# 5.net
KiCad netlist of a schematic drawn in Altium Designer
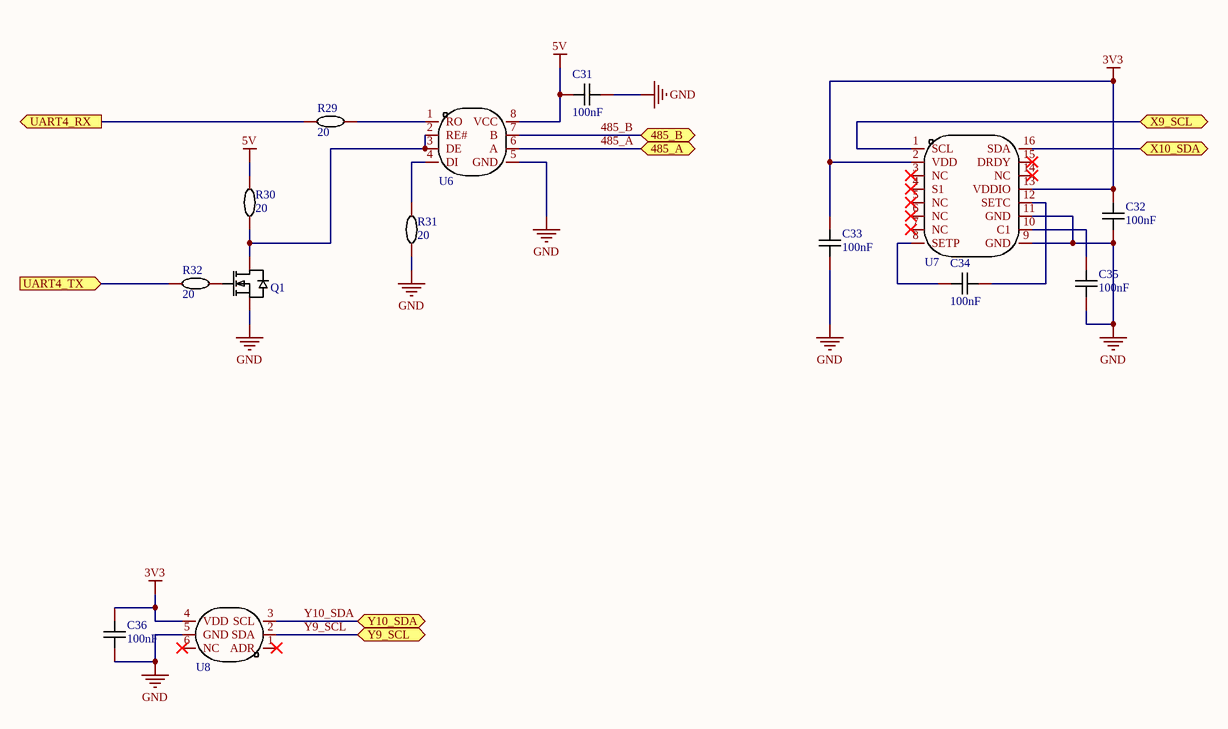
[diagram p0: 5_传感器.SchDoc]

(export (version "E")
  (design (tool "Eeschema 10.0.6"))
  (components
    (comp (ref "C31")
      (value "100nF")
      (footprint "0402C")
      (fields (field (name "NAME") "100nF"))
      (libsource (lib "2_传感器.schdoc") (part "CAP_0402"))
    )
    (comp (ref "C32")
      (value "100nF")
      (footprint "0402C")
      (fields (field (name "NAME") "100nF"))
      (libsource (lib "2_传感器.schdoc") (part "CAP_0402"))
    )
    (comp (ref "C33")
      (value "100nF")
      (footprint "0402C")
      (fields (field (name "NAME") "100nF"))
      (libsource (lib "2_传感器.schdoc") (part "CAP_0402"))
    )
    (comp (ref "C34")
      (value "100nF")
      (footprint "0402C")
      (fields (field (name "NAME") "100nF"))
      (libsource (lib "2_传感器.schdoc") (part "CAP_0402"))
    )
    (comp (ref "C35")
      (value "100nF")
      (footprint "0402C")
      (fields (field (name "NAME") "100nF"))
      (libsource (lib "2_传感器.schdoc") (part "CAP_0402"))
    )
    (comp (ref "C36")
      (value "100nF")
      (footprint "0402C")
      (fields (field (name "NAME") "100nF"))
      (libsource (lib "2_传感器.schdoc") (part "CAP_0402"))
    )
    (comp (ref "Q1")
      (value "2N7002")
      (footprint "SOT-23-3_L2.9-W1.3-P1.90-LS2.4-BR")
      (libsource (lib "2_传感器.schdoc") (part "2N7002_C8545"))
    )
    (comp (ref "R29")
      (value "20")
      (footprint "0402R")
      (fields (field (name "NAME") "20"))
      (libsource (lib "2_传感器.schdoc") (part "Res_0402"))
    )
    (comp (ref "R30")
      (value "20")
      (footprint "0402R")
      (fields (field (name "NAME") "20"))
      (libsource (lib "2_传感器.schdoc") (part "Res_0402"))
    )
    (comp (ref "R31")
      (value "20")
      (footprint "0402R")
      (fields (field (name "NAME") "20"))
      (libsource (lib "2_传感器.schdoc") (part "Res_0402"))
    )
    (comp (ref "R32")
      (value "20")
      (footprint "0402R")
      (fields (field (name "NAME") "20"))
      (libsource (lib "2_传感器.schdoc") (part "Res_0402"))
    )
    (comp (ref "U6")
      (value "MAX3485ECSA+")
      (footprint "SOIC-8_L4.9-W3.9-P1.27-LS6.0-BL")
      (libsource (lib "2_传感器.schdoc") (part "MAX3485ECSA+"))
    )
    (comp (ref "U7")
      (value "QMC5883L")
      (footprint "LGA-16_L3.0-W3.0-P0.50-BL_SQ")
      (libsource (lib "2_传感器.schdoc") (part "QMC5883L"))
    )
    (comp (ref "U8")
      (value "AHT10")
      (footprint "SENSOR-SMD_AHT10")
      (libsource (lib "2_传感器.schdoc") (part "AHT10"))
    )
  )
  (nets
    (net (code "1") (name "/485_A") (class "Default")
      (node (ref "U6") (pin "6") (pinfunction "A_6") (pintype "passive"))
    )
    (net (code "2") (name "/485_B") (class "Default")
      (node (ref "U6") (pin "7") (pinfunction "B_7") (pintype "passive"))
    )
    (net (code "3") (name "/UART4_RX") (class "Default")
      (node (ref "R29") (pin "1") (pinfunction "1_1") (pintype "passive"))
    )
    (net (code "4") (name "/UART4_TX") (class "Default")
      (node (ref "R32") (pin "1") (pinfunction "1_1") (pintype "passive"))
    )
    (net (code "5") (name "/X9_SCL") (class "Default")
      (node (ref "U7") (pin "1") (pinfunction "SCL_1") (pintype "passive"))
    )
    (net (code "6") (name "/X10_SDA") (class "Default")
      (node (ref "U7") (pin "16") (pinfunction "SDA_16") (pintype "passive"))
    )
    (net (code "7") (name "/Y9_SCL") (class "Default")
      (node (ref "U8") (pin "2") (pinfunction "SDA_2") (pintype "passive"))
    )
    (net (code "8") (name "/Y10_SDA") (class "Default")
      (node (ref "U8") (pin "3") (pinfunction "SCL_3") (pintype "passive"))
    )
    (net (code "9") (name "3V3") (class "Default")
      (node (ref "C32") (pin "1") (pinfunction "1_1") (pintype "passive"))
      (node (ref "C33") (pin "2") (pinfunction "2_2") (pintype "passive"))
      (node (ref "C36") (pin "1") (pinfunction "1_1") (pintype "passive"))
      (node (ref "U7") (pin "13") (pinfunction "VDDIO_13") (pintype "passive"))
      (node (ref "U7") (pin "2") (pinfunction "VDD_2") (pintype "passive"))
      (node (ref "U8") (pin "4") (pinfunction "VDD_4") (pintype "passive"))
    )
    (net (code "10") (name "5V") (class "Default")
      (node (ref "C31") (pin "2") (pinfunction "2_2") (pintype "passive"))
      (node (ref "R30") (pin "2") (pinfunction "2_2") (pintype "passive"))
      (node (ref "U6") (pin "8") (pinfunction "VCC_8") (pintype "passive"))
    )
    (net (code "11") (name "GND") (class "Default")
      (node (ref "C31") (pin "1") (pinfunction "1_1") (pintype "passive"))
      (node (ref "C32") (pin "2") (pinfunction "2_2") (pintype "passive"))
      (node (ref "C33") (pin "1") (pinfunction "1_1") (pintype "passive"))
      (node (ref "C35") (pin "2") (pinfunction "2_2") (pintype "passive"))
      (node (ref "C36") (pin "2") (pinfunction "2_2") (pintype "passive"))
      (node (ref "Q1") (pin "2") (pinfunction "S_2") (pintype "passive"))
      (node (ref "R31") (pin "1") (pinfunction "1_1") (pintype "passive"))
      (node (ref "U6") (pin "5") (pinfunction "GND_5") (pintype "passive"))
      (node (ref "U7") (pin "11") (pinfunction "GND_11") (pintype "passive"))
      (node (ref "U7") (pin "9") (pinfunction "GND_9") (pintype "passive"))
      (node (ref "U8") (pin "5") (pinfunction "GND_5") (pintype "passive"))
    )
    (net (code "12") (name "Net-(Q1-D)") (class "Default")
      (node (ref "Q1") (pin "3") (pinfunction "D_3") (pintype "passive"))
      (node (ref "R30") (pin "1") (pinfunction "1_1") (pintype "passive"))
      (node (ref "U6") (pin "2") (pinfunction "RE#_2") (pintype "passive"))
      (node (ref "U6") (pin "3") (pinfunction "DE_3") (pintype "passive"))
    )
    (net (code "13") (name "Net-(U6-DI)") (class "Default")
      (node (ref "R31") (pin "2") (pinfunction "2_2") (pintype "passive"))
      (node (ref "U6") (pin "4") (pinfunction "DI_4") (pintype "passive"))
    )
    (net (code "14") (name "Net-(U6-RO)") (class "Default")
      (node (ref "R29") (pin "2") (pinfunction "2_2") (pintype "passive"))
      (node (ref "U6") (pin "1") (pinfunction "RO_1") (pintype "passive"))
    )
    (net (code "15") (name "Net-(U7-C1)") (class "Default")
      (node (ref "C35") (pin "1") (pinfunction "1_1") (pintype "passive"))
      (node (ref "U7") (pin "10") (pinfunction "C1_10") (pintype "passive"))
    )
    (net (code "16") (name "Net-(U7-SETC)") (class "Default")
      (node (ref "C34") (pin "1") (pinfunction "1_1") (pintype "passive"))
      (node (ref "U7") (pin "12") (pinfunction "SETC_12") (pintype "passive"))
    )
    (net (code "17") (name "Net-(U7-SETP)") (class "Default")
      (node (ref "C34") (pin "2") (pinfunction "2_2") (pintype "passive"))
      (node (ref "U7") (pin "8") (pinfunction "SETP_8") (pintype "passive"))
    )
    (net (code "18") (name "unconnected-(Q1-G-Pad1)") (class "Default")
      (node (ref "Q1") (pin "1") (pinfunction "G_1") (pintype "passive"))
    )
    (net (code "19") (name "unconnected-(R32-Pad2)") (class "Default")
      (node (ref "R32") (pin "2") (pinfunction "2_2") (pintype "passive"))
    )
    (net (code "20") (name "unconnected-(U7-DRDY-Pad15)") (class "Default")
      (node (ref "U7") (pin "15") (pinfunction "DRDY_15") (pintype "passive+no_connect"))
    )
    (net (code "21") (name "unconnected-(U7-NC-Pad3)") (class "Default")
      (node (ref "U7") (pin "3") (pinfunction "NC_3") (pintype "passive+no_connect"))
    )
    (net (code "22") (name "unconnected-(U7-NC-Pad5)") (class "Default")
      (node (ref "U7") (pin "5") (pinfunction "NC_5") (pintype "passive+no_connect"))
    )
    (net (code "23") (name "unconnected-(U7-NC-Pad6)") (class "Default")
      (node (ref "U7") (pin "6") (pinfunction "NC_6") (pintype "passive+no_connect"))
    )
    (net (code "24") (name "unconnected-(U7-NC-Pad7)") (class "Default")
      (node (ref "U7") (pin "7") (pinfunction "NC_7") (pintype "passive+no_connect"))
    )
    (net (code "25") (name "unconnected-(U7-NC-Pad14)") (class "Default")
      (node (ref "U7") (pin "14") (pinfunction "NC_14") (pintype "passive+no_connect"))
    )
    (net (code "26") (name "unconnected-(U7-S1-Pad4)") (class "Default")
      (node (ref "U7") (pin "4") (pinfunction "S1_4") (pintype "passive+no_connect"))
    )
    (net (code "27") (name "unconnected-(U8-ADR-Pad1)") (class "Default")
      (node (ref "U8") (pin "1") (pinfunction "ADR_1") (pintype "passive+no_connect"))
    )
    (net (code "28") (name "unconnected-(U8-NC-Pad6)") (class "Default")
      (node (ref "U8") (pin "6") (pinfunction "NC_6") (pintype "passive+no_connect"))
    )
  )
)
